# H3_Power.net
KiCad netlist of a schematic drawn in Altium Designer
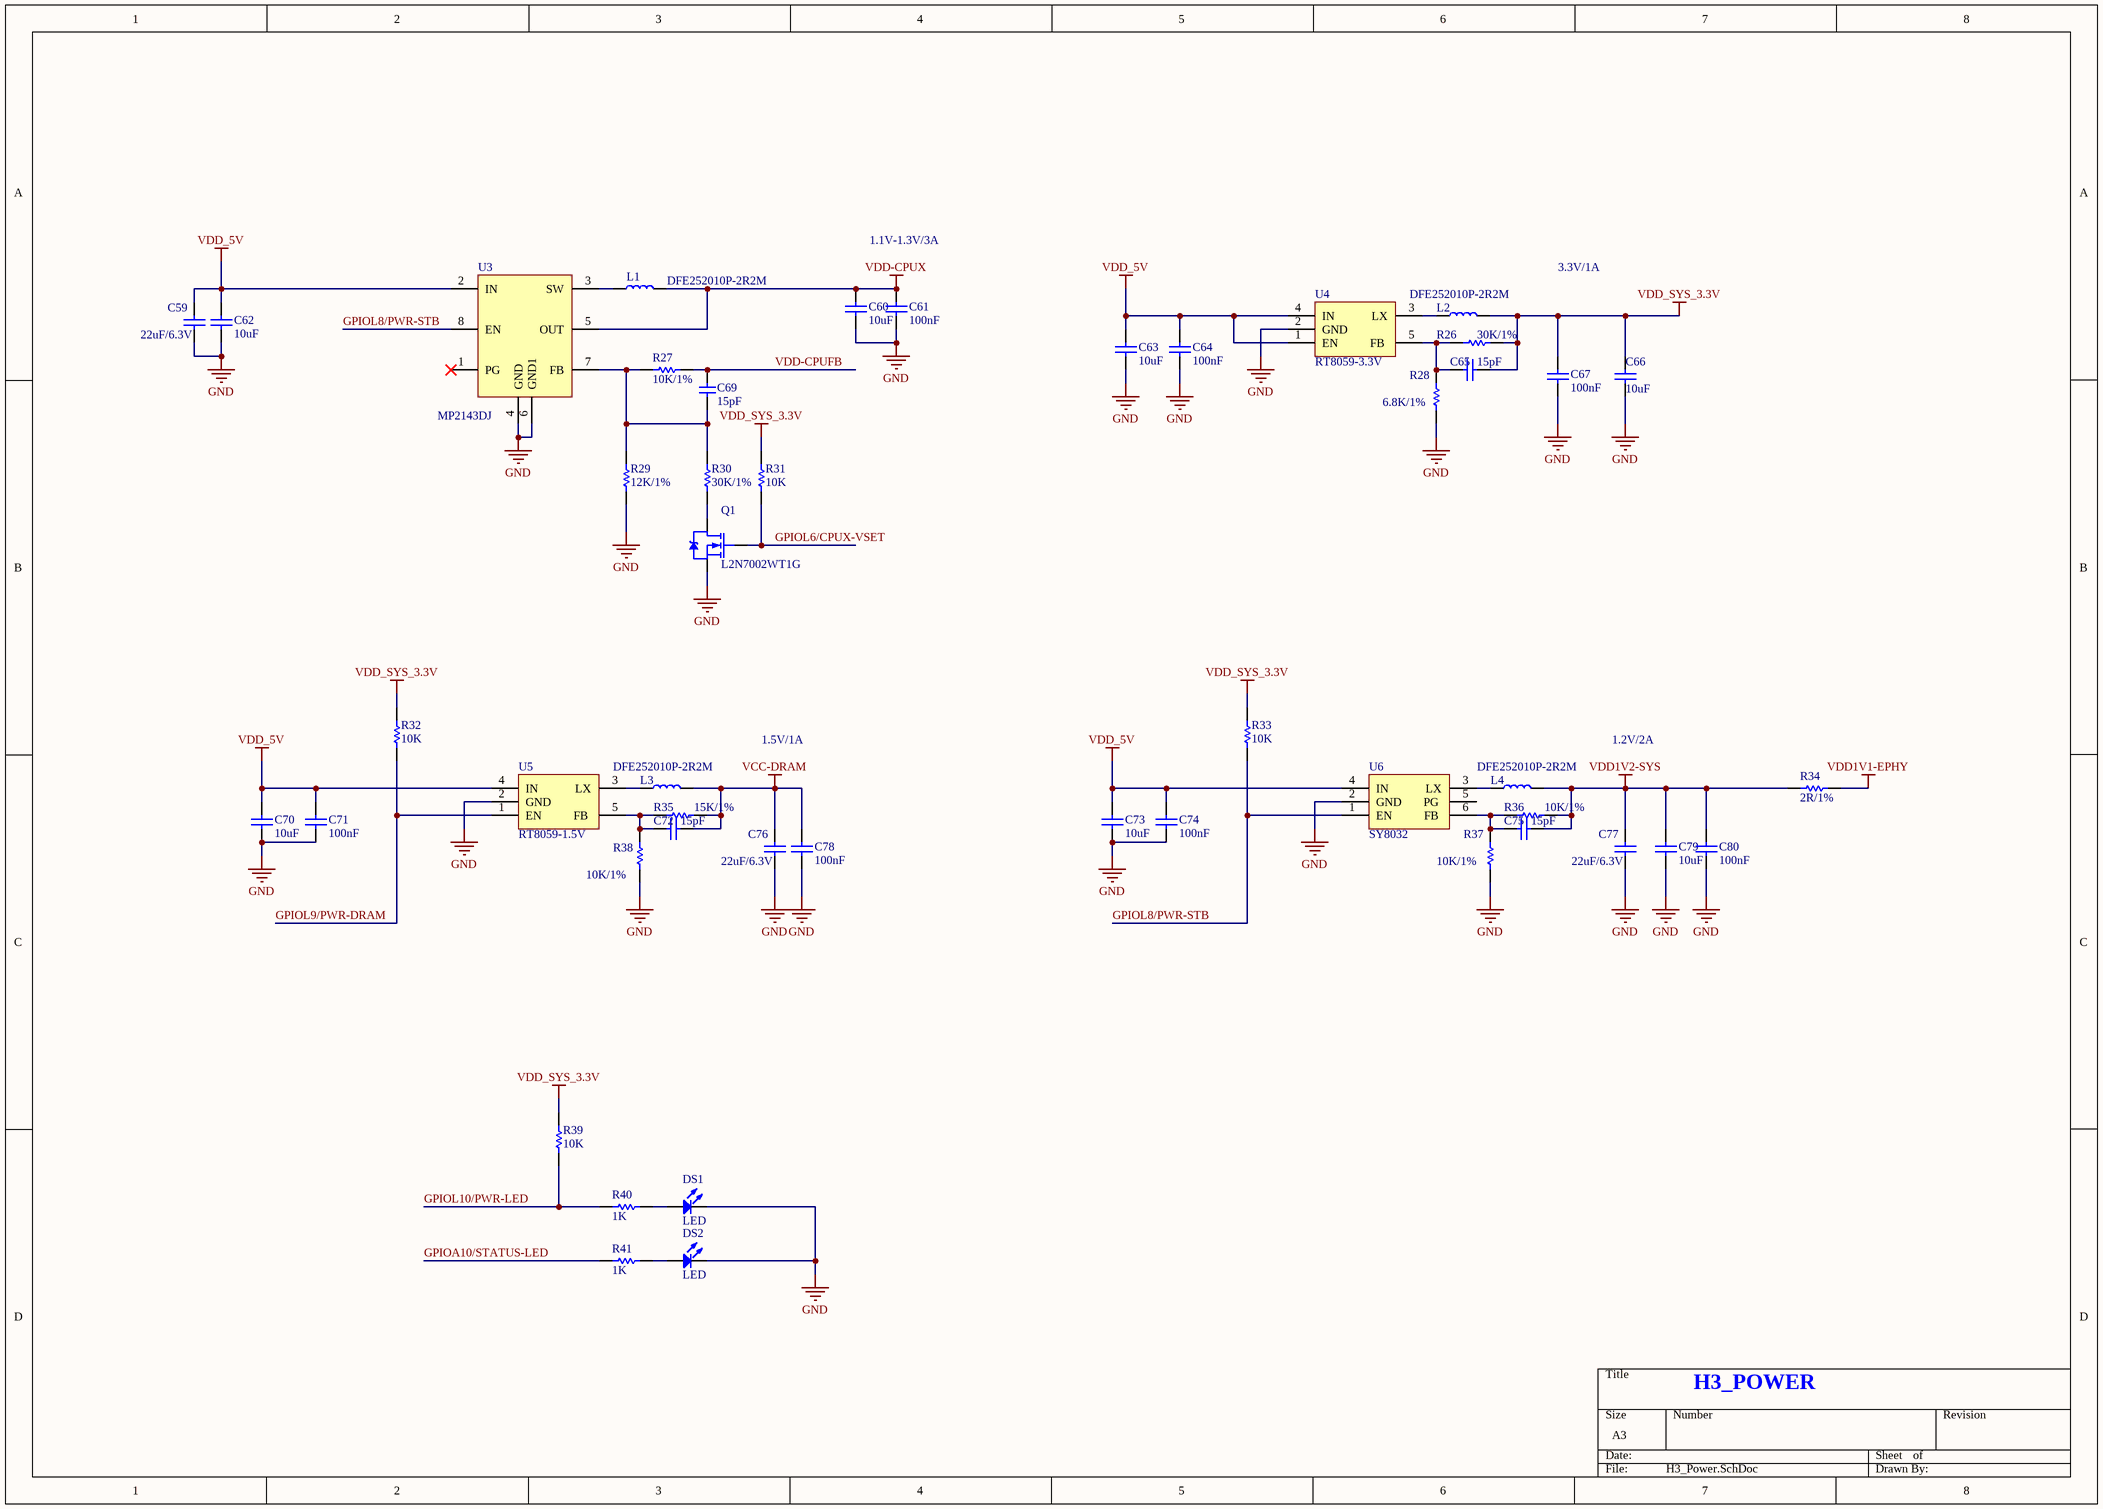
[diagram p0: H3_Power.SchDoc]

(export (version "E")
  (design (tool "Eeschema 10.0.6"))
  (components
    (comp (ref "C59")
      (value "22uF/6.3V")
      (footprint "H3_Core:C0603")
      (description "电容")
      (fields (field (name "PUBLISHER") "Altium Limited"))
      (libsource (lib "Devices") (part "C0603"))
    )
    (comp (ref "C60")
      (value "10uF")
      (footprint "H3_Core:C0603")
      (description "电容")
      (fields (field (name "PUBLISHER") "Altium Limited"))
      (libsource (lib "Devices") (part "C0603"))
    )
    (comp (ref "C61")
      (value "100nF")
      (footprint "H3_Core:C0402")
      (description "电容")
      (fields (field (name "PUBLISHER") "Altium Limited"))
      (libsource (lib "Devices") (part "C0402"))
    )
    (comp (ref "C62")
      (value "10uF")
      (footprint "H3_Core:C0603")
      (description "电容")
      (fields (field (name "PUBLISHER") "Altium Limited"))
      (libsource (lib "Devices") (part "C0603"))
    )
    (comp (ref "C63")
      (value "10uF")
      (footprint "H3_Core:C0603")
      (description "电容")
      (fields (field (name "PUBLISHER") "Altium Limited"))
      (libsource (lib "Devices") (part "C0603"))
    )
    (comp (ref "C64")
      (value "100nF")
      (footprint "H3_Core:C0402")
      (description "电容")
      (fields (field (name "PUBLISHER") "Altium Limited"))
      (libsource (lib "Devices") (part "C0402"))
    )
    (comp (ref "C65")
      (value "15pF")
      (footprint "H3_Core:C0402")
      (description "电容")
      (fields (field (name "PUBLISHER") "Altium Limited"))
      (libsource (lib "Devices") (part "C0402"))
    )
    (comp (ref "C66")
      (value "10uF")
      (footprint "H3_Core:C0603")
      (description "电容")
      (fields (field (name "PUBLISHER") "Altium Limited"))
      (libsource (lib "Devices") (part "C0603"))
    )
    (comp (ref "C67")
      (value "100nF")
      (footprint "H3_Core:C0402")
      (description "电容")
      (fields (field (name "PUBLISHER") "Altium Limited"))
      (libsource (lib "Devices") (part "C0402"))
    )
    (comp (ref "C69")
      (value "15pF")
      (footprint "H3_Core:C0402")
      (description "电容")
      (fields (field (name "PUBLISHER") "Altium Limited"))
      (libsource (lib "Devices") (part "C"))
    )
    (comp (ref "C70")
      (value "10uF")
      (footprint "H3_Core:C0603")
      (description "电容")
      (fields (field (name "PUBLISHER") "Altium Limited"))
      (libsource (lib "Devices") (part "C0603"))
    )
    (comp (ref "C71")
      (value "100nF")
      (footprint "H3_Core:C0402")
      (description "电容")
      (fields (field (name "PUBLISHER") "Altium Limited"))
      (libsource (lib "Devices") (part "C0402"))
    )
    (comp (ref "C72")
      (value "15pF")
      (footprint "H3_Core:C0402")
      (description "电容")
      (fields (field (name "PUBLISHER") "Altium Limited"))
      (libsource (lib "Devices") (part "C0402"))
    )
    (comp (ref "C73")
      (value "10uF")
      (footprint "H3_Core:C0603")
      (description "电容")
      (fields (field (name "PUBLISHER") "Altium Limited"))
      (libsource (lib "Devices") (part "C0603"))
    )
    (comp (ref "C74")
      (value "100nF")
      (footprint "H3_Core:C0402")
      (description "电容")
      (fields (field (name "PUBLISHER") "Altium Limited"))
      (libsource (lib "Devices") (part "C0402"))
    )
    (comp (ref "C75")
      (value "15pF")
      (footprint "H3_Core:C0402")
      (description "电容")
      (fields (field (name "PUBLISHER") "Altium Limited"))
      (libsource (lib "Devices") (part "C0402"))
    )
    (comp (ref "C76")
      (value "22uF/6.3V")
      (footprint "H3_Core:C0603")
      (description "电容")
      (fields (field (name "PUBLISHER") "Altium Limited"))
      (libsource (lib "Devices") (part "C0603"))
    )
    (comp (ref "C77")
      (value "22uF/6.3V")
      (footprint "H3_Core:C0603")
      (description "电容")
      (fields (field (name "PUBLISHER") "Altium Limited"))
      (libsource (lib "Devices") (part "C0603"))
    )
    (comp (ref "C78")
      (value "100nF")
      (footprint "H3_Core:C0402")
      (description "电容")
      (fields (field (name "PUBLISHER") "Altium Limited"))
      (libsource (lib "Devices") (part "C0402"))
    )
    (comp (ref "C79")
      (value "10uF")
      (footprint "H3_Core:C0603")
      (description "电容")
      (fields (field (name "PUBLISHER") "Altium Limited"))
      (libsource (lib "Devices") (part "C0603"))
    )
    (comp (ref "C80")
      (value "100nF")
      (footprint "H3_Core:C0402")
      (description "电容")
      (fields (field (name "PUBLISHER") "Altium Limited"))
      (libsource (lib "Devices") (part "C0402"))
    )
    (comp (ref "DS1")
      (value "LED")
      (footprint "H3_Core:LED0603")
      (description "Typical RED, GREEN, YELLOW, AMBER GaAs LED")
      (fields (field (name "PUBLISHER") "Altium Limited"))
      (libsource (lib "Devices") (part "LED"))
    )
    (comp (ref "DS2")
      (value "LED")
      (footprint "H3_Core:LED0603")
      (description "Typical RED, GREEN, YELLOW, AMBER GaAs LED")
      (fields (field (name "PUBLISHER") "Altium Limited"))
      (libsource (lib "Devices") (part "LED"))
    )
    (comp (ref "L1")
      (value "DFE252010P-2R2M")
      (footprint "L2520")
      (description "电感")
      (libsource (lib "Devices") (part "L"))
    )
    (comp (ref "L2")
      (value "DFE252010P-2R2M")
      (footprint "L2520")
      (description "电感")
      (libsource (lib "Devices") (part "L"))
    )
    (comp (ref "L3")
      (value "DFE252010P-2R2M")
      (footprint "L2520")
      (description "电感")
      (libsource (lib "Devices") (part "L"))
    )
    (comp (ref "L4")
      (value "DFE252010P-2R2M")
      (footprint "L2520")
      (description "电感")
      (libsource (lib "Devices") (part "L"))
    )
    (comp (ref "Q1")
      (value "L2N7002WT1G")
      (footprint "H3_Core:SOT-23-3L")
      (description "N-Channel Power MOSFET")
      (fields (field (name "PUBLISHER") "Altium Limited"))
      (libsource (lib "Devices") (part "NMOS-2"))
    )
    (comp (ref "R26")
      (value "30K/1%")
      (footprint "H3_Core:R0402")
      (description "电阻")
      (fields (field (name "PUBLISHER") "Altium Limited"))
      (libsource (lib "Devices") (part "RES0402"))
    )
    (comp (ref "R27")
      (value "10K/1%")
      (footprint "H3_Core:R0402")
      (description "电阻")
      (fields (field (name "PUBLISHER") "Altium Limited"))
      (libsource (lib "Devices") (part "RES0402"))
    )
    (comp (ref "R28")
      (value "6.8K/1%")
      (footprint "H3_Core:R0402")
      (description "电阻")
      (fields (field (name "PUBLISHER") "Altium Limited"))
      (libsource (lib "Devices") (part "RES0402"))
    )
    (comp (ref "R29")
      (value "12K/1%")
      (footprint "H3_Core:R0402")
      (description "电阻")
      (fields (field (name "PUBLISHER") "Altium Limited"))
      (libsource (lib "Devices") (part "RES0402"))
    )
    (comp (ref "R30")
      (value "30K/1%")
      (footprint "H3_Core:R0402")
      (description "电阻")
      (fields (field (name "PUBLISHER") "Altium Limited"))
      (libsource (lib "Devices") (part "RES0402"))
    )
    (comp (ref "R31")
      (value "10K")
      (footprint "H3_Core:R0402")
      (description "电阻")
      (fields (field (name "PUBLISHER") "Altium Limited"))
      (libsource (lib "Devices") (part "RES0402"))
    )
    (comp (ref "R32")
      (value "10K")
      (footprint "H3_Core:R0402")
      (description "电阻")
      (fields (field (name "PUBLISHER") "Altium Limited"))
      (libsource (lib "Devices") (part "RES0402"))
    )
    (comp (ref "R33")
      (value "10K")
      (footprint "H3_Core:R0402")
      (description "电阻")
      (fields (field (name "PUBLISHER") "Altium Limited"))
      (libsource (lib "Devices") (part "RES0402"))
    )
    (comp (ref "R34")
      (value "2R/1%")
      (footprint "H3_Core:R0402")
      (description "电阻")
      (fields (field (name "PUBLISHER") "Altium Limited"))
      (libsource (lib "Devices") (part "RES0402"))
    )
    (comp (ref "R35")
      (value "15K/1%")
      (footprint "H3_Core:R0402")
      (description "电阻")
      (fields (field (name "PUBLISHER") "Altium Limited"))
      (libsource (lib "Devices") (part "RES0402"))
    )
    (comp (ref "R36")
      (value "10K/1%")
      (footprint "H3_Core:R0402")
      (description "电阻")
      (fields (field (name "PUBLISHER") "Altium Limited"))
      (libsource (lib "Devices") (part "RES0402"))
    )
    (comp (ref "R37")
      (value "10K/1%")
      (footprint "H3_Core:R0402")
      (description "电阻")
      (fields (field (name "PUBLISHER") "Altium Limited"))
      (libsource (lib "Devices") (part "RES0402"))
    )
    (comp (ref "R38")
      (value "10K/1%")
      (footprint "H3_Core:R0402")
      (description "电阻")
      (fields (field (name "PUBLISHER") "Altium Limited"))
      (libsource (lib "Devices") (part "RES0402"))
    )
    (comp (ref "R39")
      (value "10K")
      (footprint "H3_Core:R0402")
      (description "电阻")
      (fields (field (name "PUBLISHER") "Altium Limited"))
      (libsource (lib "Devices") (part "RES0402"))
    )
    (comp (ref "R40")
      (value "1K")
      (footprint "H3_Core:R0402")
      (description "电阻")
      (fields (field (name "PUBLISHER") "Altium Limited"))
      (libsource (lib "Devices") (part "RES0402"))
    )
    (comp (ref "R41")
      (value "1K")
      (footprint "H3_Core:R0402")
      (description "电阻")
      (fields (field (name "PUBLISHER") "Altium Limited"))
      (libsource (lib "Devices") (part "RES0402"))
    )
    (comp (ref "U3")
      (value "MP2143DJ")
      (footprint "H3_Core:TSOT23-8")
      (libsource (lib "IC") (part "MP2143DJ"))
    )
    (comp (ref "U4")
      (value "RT8059-3.3V")
      (footprint "H3_Core:SOT-23-5")
      (description "RT8059")
      (libsource (lib "IC") (part "RT8059"))
    )
    (comp (ref "U5")
      (value "RT8059-1.5V")
      (footprint "H3_Core:SOT-23-5")
      (description "RT8059")
      (libsource (lib "IC") (part "RT8059"))
    )
    (comp (ref "U6")
      (value "SY8032")
      (footprint "H3_Core:SOT23-6")
      (libsource (lib "H3_Core") (part "SY8032"))
    )
  )
  (nets
    (net (code "1") (name "/GPIOA10{slash}STATUS-LED") (class "Default")
      (node (ref "R41") (pin "2") (pinfunction "2_2") (pintype "passive"))
    )
    (net (code "2") (name "/GPIOL6{slash}CPUX-VSET") (class "Default")
      (node (ref "Q1") (pin "1") (pinfunction "G_1") (pintype "passive"))
      (node (ref "R31") (pin "1") (pinfunction "1_1") (pintype "passive"))
    )
    (net (code "3") (name "/GPIOL8{slash}PWR-STB") (class "Default")
      (node (ref "R33") (pin "1") (pinfunction "1_1") (pintype "passive"))
      (node (ref "U3") (pin "8") (pinfunction "EN_8") (pintype "passive"))
      (node (ref "U6") (pin "1") (pinfunction "EN_1") (pintype "passive"))
    )
    (net (code "4") (name "/GPIOL9{slash}PWR-DRAM") (class "Default")
      (node (ref "R32") (pin "1") (pinfunction "1_1") (pintype "passive"))
      (node (ref "U5") (pin "1") (pinfunction "EN_1") (pintype "passive"))
    )
    (net (code "5") (name "/GPIOL10{slash}PWR-LED") (class "Default")
      (node (ref "R39") (pin "1") (pinfunction "1_1") (pintype "passive"))
      (node (ref "R40") (pin "2") (pinfunction "2_2") (pintype "passive"))
    )
    (net (code "6") (name "/VDD-CPUFB") (class "Default")
      (node (ref "C69") (pin "2") (pinfunction "2_2") (pintype "passive"))
      (node (ref "R27") (pin "1") (pinfunction "1_1") (pintype "passive"))
    )
    (net (code "7") (name "GND") (class "Default")
      (node (ref "C59") (pin "1") (pinfunction "1_1") (pintype "passive"))
      (node (ref "C60") (pin "1") (pinfunction "1_1") (pintype "passive"))
      (node (ref "C61") (pin "2") (pinfunction "2_2") (pintype "passive"))
      (node (ref "C62") (pin "1") (pinfunction "1_1") (pintype "passive"))
      (node (ref "C63") (pin "1") (pinfunction "1_1") (pintype "passive"))
      (node (ref "C64") (pin "1") (pinfunction "1_1") (pintype "passive"))
      (node (ref "C66") (pin "1") (pinfunction "1_1") (pintype "passive"))
      (node (ref "C67") (pin "2") (pinfunction "2_2") (pintype "passive"))
      (node (ref "C70") (pin "1") (pinfunction "1_1") (pintype "passive"))
      (node (ref "C71") (pin "2") (pinfunction "2_2") (pintype "passive"))
      (node (ref "C73") (pin "1") (pinfunction "1_1") (pintype "passive"))
      (node (ref "C74") (pin "2") (pinfunction "2_2") (pintype "passive"))
      (node (ref "C76") (pin "1") (pinfunction "1_1") (pintype "passive"))
      (node (ref "C77") (pin "1") (pinfunction "1_1") (pintype "passive"))
      (node (ref "C78") (pin "2") (pinfunction "2_2") (pintype "passive"))
      (node (ref "C79") (pin "1") (pinfunction "1_1") (pintype "passive"))
      (node (ref "C80") (pin "2") (pinfunction "2_2") (pintype "passive"))
      (node (ref "DS1") (pin "2") (pinfunction "K_2") (pintype "passive"))
      (node (ref "DS2") (pin "2") (pinfunction "K_2") (pintype "passive"))
      (node (ref "Q1") (pin "3") (pinfunction "S_3") (pintype "passive"))
      (node (ref "R28") (pin "1") (pinfunction "1_1") (pintype "passive"))
      (node (ref "R29") (pin "1") (pinfunction "1_1") (pintype "passive"))
      (node (ref "R37") (pin "1") (pinfunction "1_1") (pintype "passive"))
      (node (ref "R38") (pin "1") (pinfunction "1_1") (pintype "passive"))
      (node (ref "U3") (pin "4") (pinfunction "GND_4") (pintype "passive"))
      (node (ref "U3") (pin "6") (pinfunction "GND1_6") (pintype "passive"))
      (node (ref "U4") (pin "2") (pinfunction "GND_2") (pintype "passive"))
      (node (ref "U5") (pin "2") (pinfunction "GND_2") (pintype "passive"))
      (node (ref "U6") (pin "2") (pinfunction "GND_2") (pintype "passive"))
    )
    (net (code "8") (name "Net-(DS1-A)") (class "Default")
      (node (ref "DS1") (pin "1") (pinfunction "A_1") (pintype "passive"))
      (node (ref "R40") (pin "1") (pinfunction "1_1") (pintype "passive"))
    )
    (net (code "9") (name "Net-(DS2-A)") (class "Default")
      (node (ref "DS2") (pin "1") (pinfunction "A_1") (pintype "passive"))
      (node (ref "R41") (pin "1") (pinfunction "1_1") (pintype "passive"))
    )
    (net (code "10") (name "Net-(Q1-D)") (class "Default")
      (node (ref "Q1") (pin "2") (pinfunction "D_2") (pintype "passive"))
      (node (ref "R30") (pin "1") (pinfunction "1_1") (pintype "passive"))
    )
    (net (code "11") (name "Net-(U3-FB)") (class "Default")
      (node (ref "C69") (pin "1") (pinfunction "1_1") (pintype "passive"))
      (node (ref "R27") (pin "2") (pinfunction "2_2") (pintype "passive"))
      (node (ref "R29") (pin "2") (pinfunction "2_2") (pintype "passive"))
      (node (ref "R30") (pin "2") (pinfunction "2_2") (pintype "passive"))
      (node (ref "U3") (pin "7") (pinfunction "FB_7") (pintype "passive"))
    )
    (net (code "12") (name "Net-(U3-SW)") (class "Default")
      (node (ref "L1") (pin "2") (pinfunction "2_2") (pintype "passive"))
      (node (ref "U3") (pin "3") (pinfunction "SW_3") (pintype "passive"))
    )
    (net (code "13") (name "Net-(U4-FB)") (class "Default")
      (node (ref "C65") (pin "2") (pinfunction "2_2") (pintype "passive"))
      (node (ref "R26") (pin "2") (pinfunction "2_2") (pintype "passive"))
      (node (ref "R28") (pin "2") (pinfunction "2_2") (pintype "passive"))
      (node (ref "U4") (pin "5") (pinfunction "FB_5") (pintype "passive"))
    )
    (net (code "14") (name "Net-(U4-LX)") (class "Default")
      (node (ref "L2") (pin "2") (pinfunction "2_2") (pintype "passive"))
      (node (ref "U4") (pin "3") (pinfunction "LX_3") (pintype "passive"))
    )
    (net (code "15") (name "Net-(U5-FB)") (class "Default")
      (node (ref "C72") (pin "1") (pinfunction "1_1") (pintype "passive"))
      (node (ref "R35") (pin "2") (pinfunction "2_2") (pintype "passive"))
      (node (ref "R38") (pin "2") (pinfunction "2_2") (pintype "passive"))
      (node (ref "U5") (pin "5") (pinfunction "FB_5") (pintype "passive"))
    )
    (net (code "16") (name "Net-(U5-LX)") (class "Default")
      (node (ref "L3") (pin "2") (pinfunction "2_2") (pintype "passive"))
      (node (ref "U5") (pin "3") (pinfunction "LX_3") (pintype "passive"))
    )
    (net (code "17") (name "Net-(U6-FB)") (class "Default")
      (node (ref "C75") (pin "1") (pinfunction "1_1") (pintype "passive"))
      (node (ref "R36") (pin "2") (pinfunction "2_2") (pintype "passive"))
      (node (ref "R37") (pin "2") (pinfunction "2_2") (pintype "passive"))
      (node (ref "U6") (pin "6") (pinfunction "FB_6") (pintype "passive"))
    )
    (net (code "18") (name "Net-(U6-LX)") (class "Default")
      (node (ref "L4") (pin "2") (pinfunction "2_2") (pintype "passive"))
      (node (ref "U6") (pin "3") (pinfunction "LX_3") (pintype "passive"))
    )
    (net (code "19") (name "VCC-DRAM") (class "Default")
      (node (ref "C72") (pin "2") (pinfunction "2_2") (pintype "passive"))
      (node (ref "C76") (pin "2") (pinfunction "2_2") (pintype "passive"))
      (node (ref "C78") (pin "1") (pinfunction "1_1") (pintype "passive"))
      (node (ref "L3") (pin "1") (pinfunction "1_1") (pintype "passive"))
      (node (ref "R35") (pin "1") (pinfunction "1_1") (pintype "passive"))
    )
    (net (code "20") (name "VDD-CPUX") (class "Default")
      (node (ref "C60") (pin "2") (pinfunction "2_2") (pintype "passive"))
      (node (ref "C61") (pin "1") (pinfunction "1_1") (pintype "passive"))
      (node (ref "L1") (pin "1") (pinfunction "1_1") (pintype "passive"))
      (node (ref "U3") (pin "5") (pinfunction "OUT_5") (pintype "passive"))
    )
    (net (code "21") (name "VDD1V1-EPHY") (class "Default")
      (node (ref "R34") (pin "1") (pinfunction "1_1") (pintype "passive"))
    )
    (net (code "22") (name "VDD1V2-SYS") (class "Default")
      (node (ref "C75") (pin "2") (pinfunction "2_2") (pintype "passive"))
      (node (ref "C77") (pin "2") (pinfunction "2_2") (pintype "passive"))
      (node (ref "C79") (pin "2") (pinfunction "2_2") (pintype "passive"))
      (node (ref "C80") (pin "1") (pinfunction "1_1") (pintype "passive"))
      (node (ref "L4") (pin "1") (pinfunction "1_1") (pintype "passive"))
      (node (ref "R34") (pin "2") (pinfunction "2_2") (pintype "passive"))
      (node (ref "R36") (pin "1") (pinfunction "1_1") (pintype "passive"))
    )
    (net (code "23") (name "VDD_5V") (class "Default")
      (node (ref "C59") (pin "2") (pinfunction "2_2") (pintype "passive"))
      (node (ref "C62") (pin "2") (pinfunction "2_2") (pintype "passive"))
      (node (ref "C63") (pin "2") (pinfunction "2_2") (pintype "passive"))
      (node (ref "C64") (pin "2") (pinfunction "2_2") (pintype "passive"))
      (node (ref "C70") (pin "2") (pinfunction "2_2") (pintype "passive"))
      (node (ref "C71") (pin "1") (pinfunction "1_1") (pintype "passive"))
      (node (ref "C73") (pin "2") (pinfunction "2_2") (pintype "passive"))
      (node (ref "C74") (pin "1") (pinfunction "1_1") (pintype "passive"))
      (node (ref "U3") (pin "2") (pinfunction "IN_2") (pintype "passive"))
      (node (ref "U4") (pin "1") (pinfunction "EN_1") (pintype "passive"))
      (node (ref "U4") (pin "4") (pinfunction "IN_4") (pintype "passive"))
      (node (ref "U5") (pin "4") (pinfunction "IN_4") (pintype "passive"))
      (node (ref "U6") (pin "4") (pinfunction "IN_4") (pintype "passive"))
    )
    (net (code "24") (name "VDD_SYS_3.3V") (class "Default")
      (node (ref "C65") (pin "1") (pinfunction "1_1") (pintype "passive"))
      (node (ref "C66") (pin "2") (pinfunction "2_2") (pintype "passive"))
      (node (ref "C67") (pin "1") (pinfunction "1_1") (pintype "passive"))
      (node (ref "L2") (pin "1") (pinfunction "1_1") (pintype "passive"))
      (node (ref "R26") (pin "1") (pinfunction "1_1") (pintype "passive"))
      (node (ref "R31") (pin "2") (pinfunction "2_2") (pintype "passive"))
      (node (ref "R32") (pin "2") (pinfunction "2_2") (pintype "passive"))
      (node (ref "R33") (pin "2") (pinfunction "2_2") (pintype "passive"))
      (node (ref "R39") (pin "2") (pinfunction "2_2") (pintype "passive"))
    )
    (net (code "25") (name "unconnected-(U3-PG-Pad1)") (class "Default")
      (node (ref "U3") (pin "1") (pinfunction "PG_1") (pintype "passive+no_connect"))
    )
    (net (code "26") (name "unconnected-(U6-PG-Pad5)") (class "Default")
      (node (ref "U6") (pin "5") (pinfunction "PG_5") (pintype "passive"))
    )
  )
)
